# VoiceRecognition.net
KiCad netlist of a schematic drawn in EAGLE
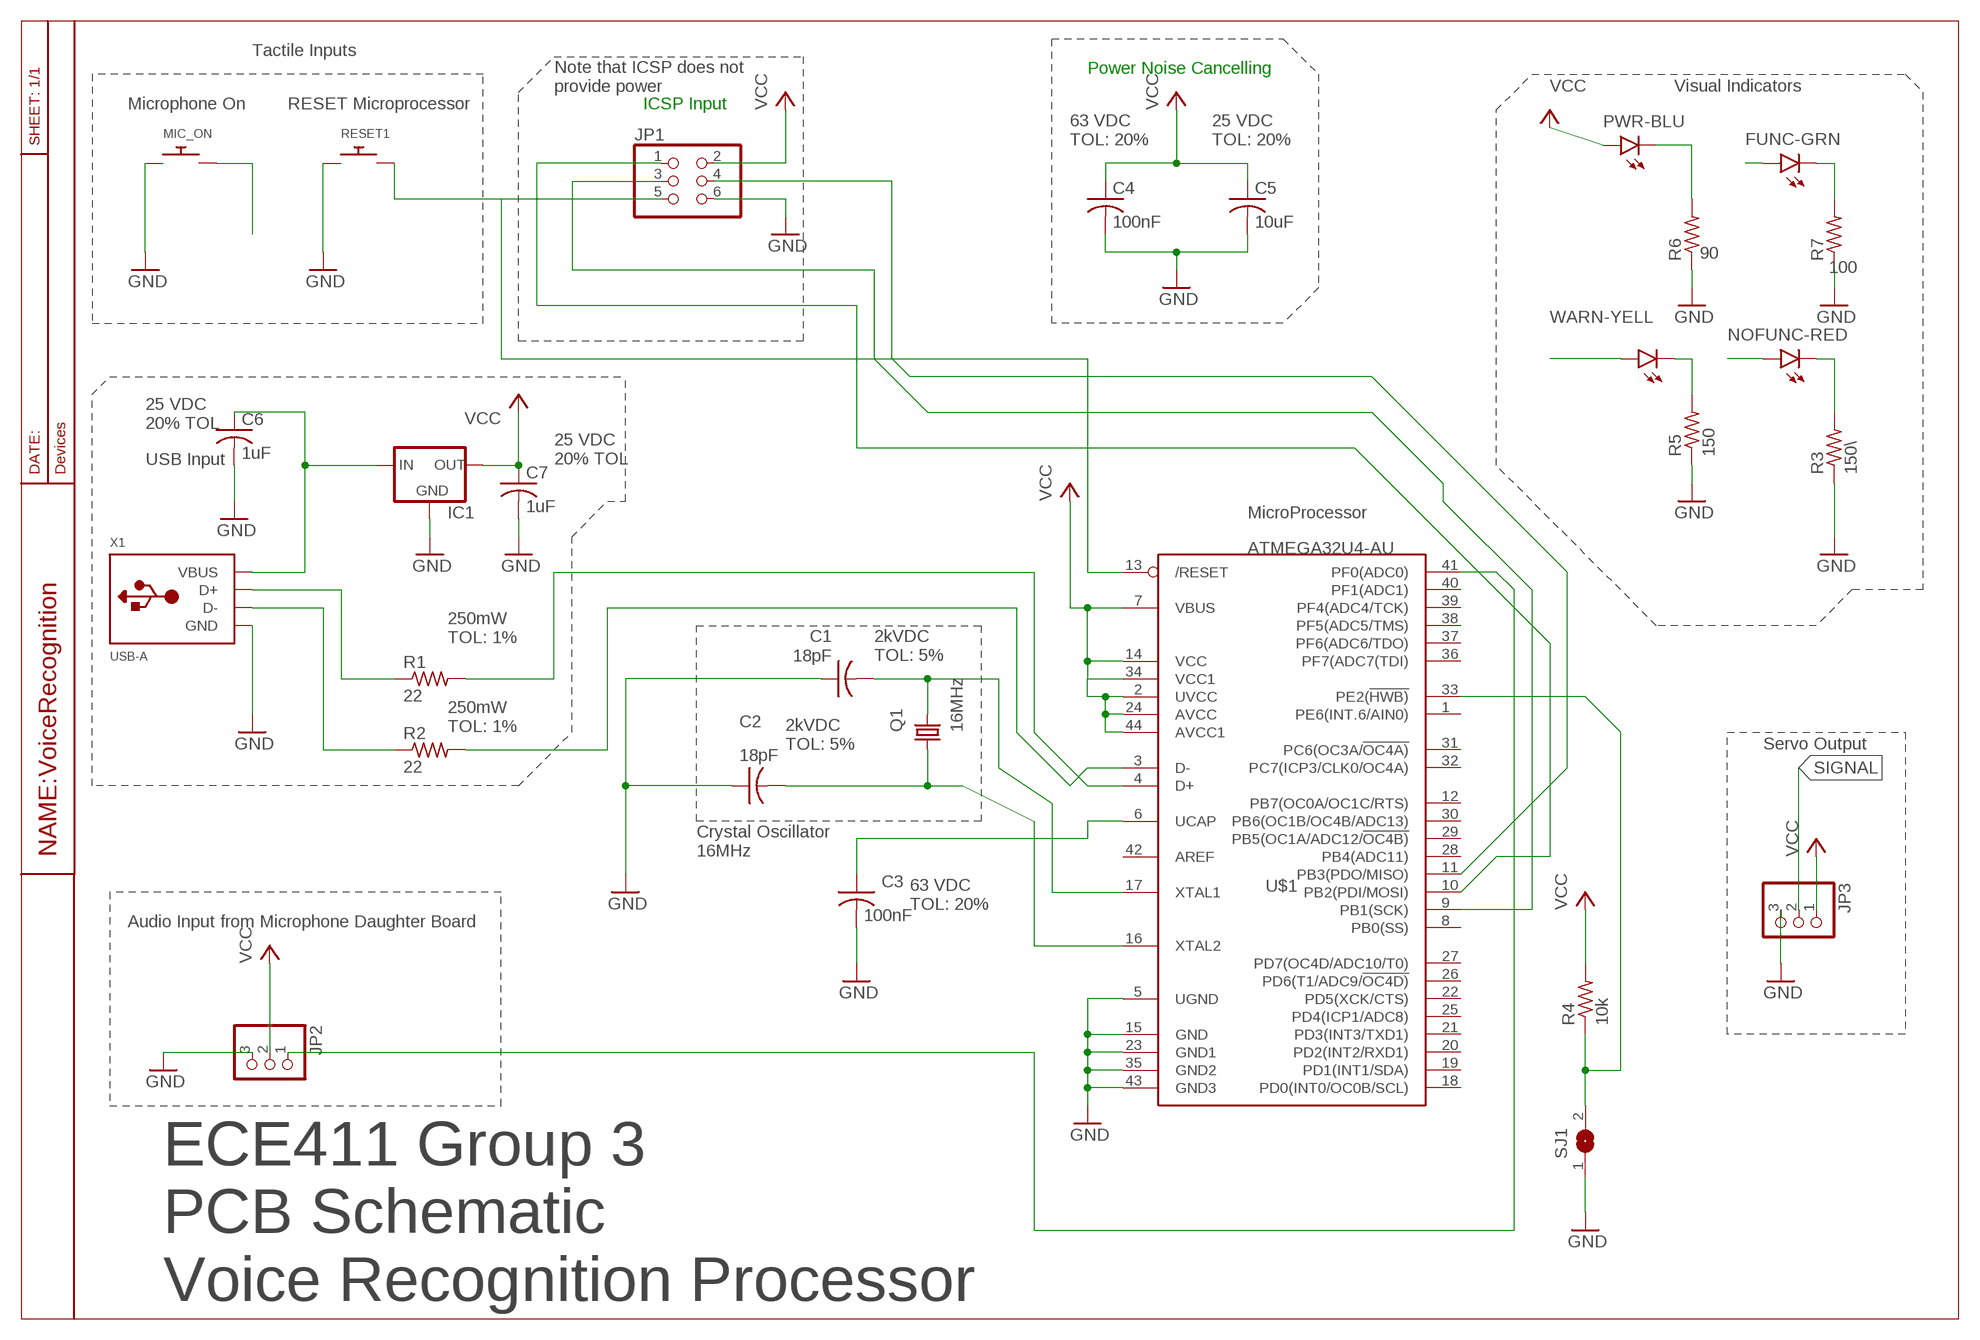
[diagram p0: schematic, sheet 1]

(export (version "E")
  (design (tool "Eeschema 10.0.6"))
  (components
    (comp (ref "C1")
      (value "18pF")
      (footprint "eagle-import:C1206")
      (libsource (lib "eagle-import") (part "C-USC1206"))
    )
    (comp (ref "C2")
      (value "18pF")
      (footprint "eagle-import:C1206")
      (libsource (lib "eagle-import") (part "C-USC1206"))
    )
    (comp (ref "C3")
      (value "100nF")
      (footprint "eagle-import:C1206")
      (libsource (lib "eagle-import") (part "C-USC1206"))
    )
    (comp (ref "C4")
      (value "100nF")
      (footprint "eagle-import:C1206")
      (libsource (lib "eagle-import") (part "C-USC1206"))
    )
    (comp (ref "C5")
      (value "10uF")
      (footprint "eagle-import:C1206")
      (libsource (lib "eagle-import") (part "C-USC1206"))
    )
    (comp (ref "C6")
      (value "1uF")
      (footprint "eagle-import:C1206")
      (libsource (lib "eagle-import") (part "C-USC1206"))
    )
    (comp (ref "C7")
      (value "1uF")
      (footprint "eagle-import:C1206")
      (libsource (lib "eagle-import") (part "C-USC1206"))
    )
    (comp (ref "IC1")
      (value "MCP1700INLINE")
      (footprint "eagle-import:TO92-INLINE")
      (libsource (lib "eagle-import") (part "MCP1700INLINE"))
    )
    (comp (ref "JP1")
      (value "PINHD-2X3")
      (footprint "eagle-import:2X03")
      (libsource (lib "eagle-import") (part "PINHD-2X3"))
    )
    (comp (ref "JP2")
      (value "PINHD-1X3")
      (footprint "eagle-import:1X03")
      (libsource (lib "eagle-import") (part "PINHD-1X3"))
    )
    (comp (ref "JP3")
      (value "PINHD-1X3")
      (footprint "eagle-import:1X03")
      (libsource (lib "eagle-import") (part "PINHD-1X3"))
    )
    (comp (ref "LED2")
      (value "LEDSMT1206")
      (footprint "eagle-import:1206")
      (libsource (lib "eagle-import") (part "LEDSMT1206"))
    )
    (comp (ref "LED3")
      (value "LEDSMT1206")
      (footprint "eagle-import:1206")
      (libsource (lib "eagle-import") (part "LEDSMT1206"))
    )
    (comp (ref "LED4")
      (value "LEDSMT1206")
      (footprint "eagle-import:1206")
      (libsource (lib "eagle-import") (part "LEDSMT1206"))
    )
    (comp (ref "MIC_ON")
      (value "SWITCH_PUSHBUTTONC&K_KSS")
      (footprint "eagle-import:BTN_CK_KSS")
      (libsource (lib "eagle-import") (part "SWITCH_PUSHBUTTONC&K_KSS"))
    )
    (comp (ref "PWR-BLU")
      (value "LEDSMT1206")
      (footprint "eagle-import:1206")
      (libsource (lib "eagle-import") (part "LEDSMT1206"))
    )
    (comp (ref "Q1")
      (value "16MHz")
      (footprint "eagle-import:CTS406")
      (libsource (lib "eagle-import") (part "CRYSTALCTS406"))
    )
    (comp (ref "R1")
      (value "22")
      (footprint "eagle-import:M1206")
      (libsource (lib "eagle-import") (part "R-US_M1206"))
    )
    (comp (ref "R2")
      (value "22")
      (footprint "eagle-import:M1206")
      (libsource (lib "eagle-import") (part "R-US_M1206"))
    )
    (comp (ref "R3")
      (value "150\\")
      (footprint "eagle-import:M1206")
      (libsource (lib "eagle-import") (part "R-US_M1206"))
    )
    (comp (ref "R4")
      (value "10k")
      (footprint "eagle-import:M1206")
      (libsource (lib "eagle-import") (part "R-US_M1206"))
    )
    (comp (ref "R5")
      (value "150")
      (footprint "eagle-import:M1206")
      (libsource (lib "eagle-import") (part "R-US_M1206"))
    )
    (comp (ref "R6")
      (value "90")
      (footprint "eagle-import:M1206")
      (libsource (lib "eagle-import") (part "R-US_M1206"))
    )
    (comp (ref "R7")
      (value "100")
      (footprint "eagle-import:M1206")
      (libsource (lib "eagle-import") (part "R-US_M1206"))
    )
    (comp (ref "RESET1")
      (value "SWITCH_PUSHBUTTONC&K_KSS")
      (footprint "eagle-import:BTN_CK_KSS")
      (libsource (lib "eagle-import") (part "SWITCH_PUSHBUTTONC&K_KSS"))
    )
    (comp (ref "SJ1")
      (value "SJW")
      (footprint "eagle-import:SJW")
      (libsource (lib "eagle-import") (part "SJW"))
    )
    (comp (ref "U$1")
      (value "ATMEGA32U4-AU")
      (footprint "eagle-import:TQFP44")
      (libsource (lib "eagle-import") (part "ATMEGA32U4-AU"))
    )
    (comp (ref "X1")
      (value "USB-A")
      (footprint "eagle-import:MOLEX_480371000")
      (libsource (lib "eagle-import") (part "USB-A"))
    )
  )
  (nets
    (net (code "1") (name "/FUNC-GRN") (class "Default")
      (node (ref "LED2") (pin "A") (pinfunction "A_A") (pintype "passive"))
    )
    (net (code "2") (name "/NOFUNC-RED") (class "Default")
      (node (ref "LED3") (pin "A") (pinfunction "A_A") (pintype "passive"))
    )
    (net (code "3") (name "GND") (class "Default")
      (node (ref "C1") (pin "1") (pinfunction "1_1") (pintype "passive"))
      (node (ref "C2") (pin "1") (pinfunction "1_1") (pintype "passive"))
      (node (ref "C3") (pin "2") (pinfunction "2_2") (pintype "passive"))
      (node (ref "C4") (pin "2") (pinfunction "2_2") (pintype "passive"))
      (node (ref "C5") (pin "2") (pinfunction "2_2") (pintype "passive"))
      (node (ref "C6") (pin "2") (pinfunction "2_2") (pintype "passive"))
      (node (ref "C7") (pin "2") (pinfunction "2_2") (pintype "passive"))
      (node (ref "IC1") (pin "1") (pinfunction "GND_1") (pintype "input"))
      (node (ref "JP1") (pin "6") (pinfunction "6_6") (pintype "passive"))
      (node (ref "JP2") (pin "3") (pinfunction "3_3") (pintype "passive"))
      (node (ref "JP3") (pin "3") (pinfunction "3_3") (pintype "passive"))
      (node (ref "MIC_ON") (pin "P$1") (pinfunction "P$1_P$1") (pintype "passive"))
      (node (ref "R3") (pin "1") (pinfunction "1_1") (pintype "passive"))
      (node (ref "R5") (pin "1") (pinfunction "1_1") (pintype "passive"))
      (node (ref "R6") (pin "1") (pinfunction "1_1") (pintype "passive"))
      (node (ref "R7") (pin "1") (pinfunction "1_1") (pintype "passive"))
      (node (ref "RESET1") (pin "P$1") (pinfunction "P$1_P$1") (pintype "passive"))
      (node (ref "SJ1") (pin "1") (pinfunction "1_1") (pintype "passive"))
      (node (ref "U$1") (pin "15") (pinfunction "GND_15") (pintype "bidirectional"))
      (node (ref "U$1") (pin "23") (pinfunction "GND1_23") (pintype "bidirectional"))
      (node (ref "U$1") (pin "35") (pinfunction "GND2_35") (pintype "bidirectional"))
      (node (ref "U$1") (pin "43") (pinfunction "GND3_43") (pintype "bidirectional"))
      (node (ref "U$1") (pin "5") (pinfunction "UGND_5") (pintype "bidirectional"))
      (node (ref "X1") (pin "4") (pinfunction "GND_4") (pintype "power_in"))
    )
    (net (code "4") (name "Net-(IC1-IN)") (class "Default")
      (node (ref "C6") (pin "1") (pinfunction "1_1") (pintype "passive"))
      (node (ref "IC1") (pin "2") (pinfunction "IN_2") (pintype "input"))
      (node (ref "X1") (pin "1") (pinfunction "VBUS_1") (pintype "power_in"))
    )
    (net (code "5") (name "Net-(LED2-PadC)") (class "Default")
      (node (ref "LED2") (pin "C") (pinfunction "C_C") (pintype "passive"))
      (node (ref "R7") (pin "2") (pinfunction "2_2") (pintype "passive"))
    )
    (net (code "6") (name "Net-(LED3-PadC)") (class "Default")
      (node (ref "LED3") (pin "C") (pinfunction "C_C") (pintype "passive"))
      (node (ref "R3") (pin "2") (pinfunction "2_2") (pintype "passive"))
    )
    (net (code "7") (name "Net-(LED4-PadC)") (class "Default")
      (node (ref "LED4") (pin "C") (pinfunction "C_C") (pintype "passive"))
      (node (ref "R5") (pin "2") (pinfunction "2_2") (pintype "passive"))
    )
    (net (code "8") (name "Net-(PWR-BLU-PadC)") (class "Default")
      (node (ref "PWR-BLU") (pin "C") (pinfunction "C_C") (pintype "passive"))
      (node (ref "R6") (pin "2") (pinfunction "2_2") (pintype "passive"))
    )
    (net (code "9") (name "Net-(Q1-2)") (class "Default")
      (node (ref "C1") (pin "2") (pinfunction "2_2") (pintype "passive"))
      (node (ref "Q1") (pin "3") (pinfunction "2_3") (pintype "passive"))
      (node (ref "U$1") (pin "17") (pinfunction "XTAL1_17") (pintype "bidirectional"))
    )
    (net (code "10") (name "Net-(U$1-D+)") (class "Default")
      (node (ref "R1") (pin "2") (pinfunction "2_2") (pintype "passive"))
      (node (ref "U$1") (pin "4") (pinfunction "D+_4") (pintype "bidirectional"))
    )
    (net (code "11") (name "Net-(U$1-D-)") (class "Default")
      (node (ref "R2") (pin "2") (pinfunction "2_2") (pintype "passive"))
      (node (ref "U$1") (pin "3") (pinfunction "D-_3") (pintype "bidirectional"))
    )
    (net (code "12") (name "Net-(U$1-PB1(SCK))") (class "Default")
      (node (ref "JP1") (pin "3") (pinfunction "3_3") (pintype "passive"))
      (node (ref "U$1") (pin "9") (pinfunction "PB1(SCK)_9") (pintype "bidirectional"))
    )
    (net (code "13") (name "Net-(U$1-PB2(PDI{slash}MOSI))") (class "Default")
      (node (ref "JP1") (pin "1") (pinfunction "1_1") (pintype "passive"))
      (node (ref "U$1") (pin "10") (pinfunction "PB2(PDI/MOSI)_10") (pintype "bidirectional"))
    )
    (net (code "14") (name "Net-(U$1-PB3(PDO{slash}MISO))") (class "Default")
      (node (ref "JP1") (pin "4") (pinfunction "4_4") (pintype "passive"))
      (node (ref "U$1") (pin "11") (pinfunction "PB3(PDO/MISO)_11") (pintype "bidirectional"))
    )
    (net (code "15") (name "Net-(U$1-PE2(~{HWB}))") (class "Default")
      (node (ref "R4") (pin "1") (pinfunction "1_1") (pintype "passive"))
      (node (ref "SJ1") (pin "2") (pinfunction "2_2") (pintype "passive"))
      (node (ref "U$1") (pin "33") (pinfunction "PE2(~{HWB})_33") (pintype "bidirectional"))
    )
    (net (code "16") (name "Net-(U$1-PF0(ADC0))") (class "Default")
      (node (ref "JP2") (pin "1") (pinfunction "1_1") (pintype "passive"))
      (node (ref "U$1") (pin "41") (pinfunction "PF0(ADC0)_41") (pintype "bidirectional"))
    )
    (net (code "17") (name "Net-(U$1-UCAP)") (class "Default")
      (node (ref "C3") (pin "1") (pinfunction "1_1") (pintype "passive"))
      (node (ref "U$1") (pin "6") (pinfunction "UCAP_6") (pintype "bidirectional"))
    )
    (net (code "18") (name "Net-(U$1-XTAL2)") (class "Default")
      (node (ref "C2") (pin "2") (pinfunction "2_2") (pintype "passive"))
      (node (ref "Q1") (pin "1") (pinfunction "1_1") (pintype "passive"))
      (node (ref "U$1") (pin "16") (pinfunction "XTAL2_16") (pintype "bidirectional"))
    )
    (net (code "19") (name "Net-(U$1-{slash}RESET)") (class "Default")
      (node (ref "JP1") (pin "5") (pinfunction "5_5") (pintype "passive"))
      (node (ref "RESET1") (pin "P$2") (pinfunction "P$2_P$2") (pintype "passive"))
      (node (ref "U$1") (pin "13") (pinfunction "/RESET_13") (pintype "bidirectional"))
    )
    (net (code "20") (name "Net-(X1-D+)") (class "Default")
      (node (ref "R1") (pin "1") (pinfunction "1_1") (pintype "passive"))
      (node (ref "X1") (pin "3") (pinfunction "D+_3") (pintype "bidirectional"))
    )
    (net (code "21") (name "Net-(X1-D-)") (class "Default")
      (node (ref "R2") (pin "1") (pinfunction "1_1") (pintype "passive"))
      (node (ref "X1") (pin "2") (pinfunction "D-_2") (pintype "bidirectional"))
    )
    (net (code "22") (name "SIGNAL") (class "Default")
      (node (ref "JP3") (pin "2") (pinfunction "2_2") (pintype "passive"))
    )
    (net (code "23") (name "VCC") (class "Default")
      (node (ref "C4") (pin "1") (pinfunction "1_1") (pintype "passive"))
      (node (ref "C5") (pin "1") (pinfunction "1_1") (pintype "passive"))
      (node (ref "C7") (pin "1") (pinfunction "1_1") (pintype "passive"))
      (node (ref "IC1") (pin "3") (pinfunction "OUT_3") (pintype "passive"))
      (node (ref "JP1") (pin "2") (pinfunction "2_2") (pintype "passive"))
      (node (ref "JP2") (pin "2") (pinfunction "2_2") (pintype "passive"))
      (node (ref "JP3") (pin "1") (pinfunction "1_1") (pintype "passive"))
      (node (ref "PWR-BLU") (pin "A") (pinfunction "A_A") (pintype "passive"))
      (node (ref "R4") (pin "2") (pinfunction "2_2") (pintype "passive"))
      (node (ref "U$1") (pin "14") (pinfunction "VCC_14") (pintype "bidirectional"))
      (node (ref "U$1") (pin "2") (pinfunction "UVCC_2") (pintype "bidirectional"))
      (node (ref "U$1") (pin "24") (pinfunction "AVCC_24") (pintype "bidirectional"))
      (node (ref "U$1") (pin "34") (pinfunction "VCC1_34") (pintype "bidirectional"))
      (node (ref "U$1") (pin "44") (pinfunction "AVCC1_44") (pintype "bidirectional"))
      (node (ref "U$1") (pin "7") (pinfunction "VBUS_7") (pintype "bidirectional"))
    )
    (net (code "24") (name "unconnected-(LED4-PadA)") (class "Default")
      (node (ref "LED4") (pin "A") (pinfunction "A_A") (pintype "passive"))
    )
    (net (code "25") (name "unconnected-(MIC_ON-PadP$2)") (class "Default")
      (node (ref "MIC_ON") (pin "P$2") (pinfunction "P$2_P$2") (pintype "passive"))
    )
    (net (code "26") (name "unconnected-(U$1-AREF-Pad42)") (class "Default")
      (node (ref "U$1") (pin "42") (pinfunction "AREF_42") (pintype "bidirectional"))
    )
    (net (code "27") (name "unconnected-(U$1-PB0(SS)-Pad8)") (class "Default")
      (node (ref "U$1") (pin "8") (pinfunction "PB0(SS)_8") (pintype "bidirectional"))
    )
    (net (code "28") (name "unconnected-(U$1-PB4(ADC11)-Pad28)") (class "Default")
      (node (ref "U$1") (pin "28") (pinfunction "PB4(ADC11)_28") (pintype "bidirectional"))
    )
    (net (code "29") (name "unconnected-(U$1-PB5(OC1A{slash}ADC12{slash}~{OC4B})-Pad29)") (class "Default")
      (node (ref "U$1") (pin "29") (pinfunction "PB5(OC1A/ADC12/~{OC4B})_29") (pintype "bidirectional"))
    )
    (net (code "30") (name "unconnected-(U$1-PB6(OC1B{slash}OC4B{slash}ADC13)-Pad30)") (class "Default")
      (node (ref "U$1") (pin "30") (pinfunction "PB6(OC1B/OC4B/ADC13)_30") (pintype "bidirectional"))
    )
    (net (code "31") (name "unconnected-(U$1-PB7(OC0A{slash}OC1C{slash}RTS)-Pad12)") (class "Default")
      (node (ref "U$1") (pin "12") (pinfunction "PB7(OC0A/OC1C/RTS)_12") (pintype "bidirectional"))
    )
    (net (code "32") (name "unconnected-(U$1-PC6(OC3A{slash}~{OC4A})-Pad31)") (class "Default")
      (node (ref "U$1") (pin "31") (pinfunction "PC6(OC3A/~{OC4A})_31") (pintype "bidirectional"))
    )
    (net (code "33") (name "unconnected-(U$1-PC7(ICP3{slash}CLK0{slash}OC4A)-Pad32)") (class "Default")
      (node (ref "U$1") (pin "32") (pinfunction "PC7(ICP3/CLK0/OC4A)_32") (pintype "bidirectional"))
    )
    (net (code "34") (name "unconnected-(U$1-PD0(INT0{slash}OC0B{slash}SCL)-Pad18)") (class "Default")
      (node (ref "U$1") (pin "18") (pinfunction "PD0(INT0/OC0B/SCL)_18") (pintype "bidirectional"))
    )
    (net (code "35") (name "unconnected-(U$1-PD1(INT1{slash}SDA)-Pad19)") (class "Default")
      (node (ref "U$1") (pin "19") (pinfunction "PD1(INT1/SDA)_19") (pintype "bidirectional"))
    )
    (net (code "36") (name "unconnected-(U$1-PD2(INT2{slash}RXD1)-Pad20)") (class "Default")
      (node (ref "U$1") (pin "20") (pinfunction "PD2(INT2/RXD1)_20") (pintype "bidirectional"))
    )
    (net (code "37") (name "unconnected-(U$1-PD3(INT3{slash}TXD1)-Pad21)") (class "Default")
      (node (ref "U$1") (pin "21") (pinfunction "PD3(INT3/TXD1)_21") (pintype "bidirectional"))
    )
    (net (code "38") (name "unconnected-(U$1-PD4(ICP1{slash}ADC8)-Pad25)") (class "Default")
      (node (ref "U$1") (pin "25") (pinfunction "PD4(ICP1/ADC8)_25") (pintype "bidirectional"))
    )
    (net (code "39") (name "unconnected-(U$1-PD5(XCK{slash}CTS)-Pad22)") (class "Default")
      (node (ref "U$1") (pin "22") (pinfunction "PD5(XCK/CTS)_22") (pintype "bidirectional"))
    )
    (net (code "40") (name "unconnected-(U$1-PD6(T1{slash}ADC9{slash}~{OC4D})-Pad26)") (class "Default")
      (node (ref "U$1") (pin "26") (pinfunction "PD6(T1/ADC9/~{OC4D})_26") (pintype "bidirectional"))
    )
    (net (code "41") (name "unconnected-(U$1-PD7(OC4D{slash}ADC10{slash}T0)-Pad27)") (class "Default")
      (node (ref "U$1") (pin "27") (pinfunction "PD7(OC4D/ADC10/T0)_27") (pintype "bidirectional"))
    )
    (net (code "42") (name "unconnected-(U$1-PE6(INT.6{slash}AIN0)-Pad1)") (class "Default")
      (node (ref "U$1") (pin "1") (pinfunction "PE6(INT.6/AIN0)_1") (pintype "bidirectional"))
    )
    (net (code "43") (name "unconnected-(U$1-PF1(ADC1)-Pad40)") (class "Default")
      (node (ref "U$1") (pin "40") (pinfunction "PF1(ADC1)_40") (pintype "bidirectional"))
    )
    (net (code "44") (name "unconnected-(U$1-PF4(ADC4{slash}TCK)-Pad39)") (class "Default")
      (node (ref "U$1") (pin "39") (pinfunction "PF4(ADC4/TCK)_39") (pintype "bidirectional"))
    )
    (net (code "45") (name "unconnected-(U$1-PF5(ADC5{slash}TMS)-Pad38)") (class "Default")
      (node (ref "U$1") (pin "38") (pinfunction "PF5(ADC5/TMS)_38") (pintype "bidirectional"))
    )
    (net (code "46") (name "unconnected-(U$1-PF6(ADC6{slash}TDO)-Pad37)") (class "Default")
      (node (ref "U$1") (pin "37") (pinfunction "PF6(ADC6/TDO)_37") (pintype "bidirectional"))
    )
    (net (code "47") (name "unconnected-(U$1-PF7(ADC7(TDI)-Pad36)") (class "Default")
      (node (ref "U$1") (pin "36") (pinfunction "PF7(ADC7(TDI)_36") (pintype "bidirectional"))
    )
  )
)
